# MB1-LED_BUTTON.net
KiCad netlist of a schematic drawn in Altium Designer
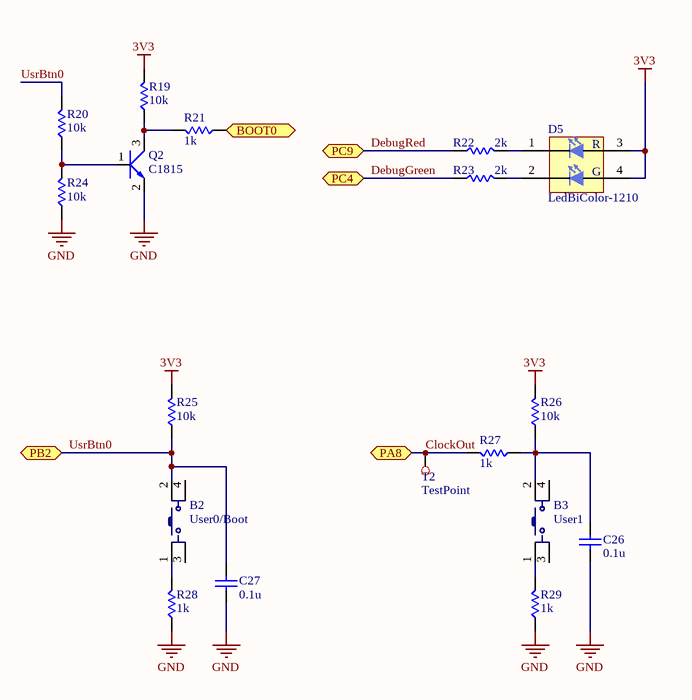
[diagram p0: MB1-LED_BUTTON.SchDoc]

(export (version "E")
  (design (tool "Eeschema 10.0.6"))
  (components
    (comp (ref "B2")
      (value "User0/Boot")
      (footprint "Horizon_SW_4pin_rectangular")
      (description "Tact switch")
      (libsource (lib "SMD_tact_sw") (part "Button"))
    )
    (comp (ref "B3")
      (value "User1")
      (footprint "Horizon_SW_4pin_rectangular")
      (description "Tact switch")
      (libsource (lib "SMD_tact_sw") (part "Button"))
    )
    (comp (ref "C26")
      (value "0.1u")
      (footprint "SM_0805_C_CERAMIC")
      (description "Non-polarity ceramic capacitor")
      (fields (field (name "Comment") "CAP_Ceramic") (field (name "PUBLISHER") "Altium Limited"))
      (libsource (lib "Copy of HLib_device_library") (part "C_Ceramic"))
    )
    (comp (ref "C27")
      (value "0.1u")
      (footprint "SM_0805_C_CERAMIC")
      (description "Non-polarity ceramic capacitor")
      (fields (field (name "Comment") "CAP_Ceramic") (field (name "PUBLISHER") "Altium Limited"))
      (libsource (lib "Copy of HLib_device_library") (part "C_Ceramic"))
    )
    (comp (ref "D5")
      (value "LedBiColor-1210")
      (footprint "Led-BiColor")
      (libsource (lib "MyLib") (part "LedBiColor-1210"))
    )
    (comp (ref "Q2") (value "C1815") (footprint "SOT23") (libsource (lib "MyLib") (part "C1815")))
    (comp (ref "R19")
      (value "10k")
      (footprint "SM_0805_R")
      (description "Resistor")
      (fields (field (name "PUBLISHER") "Altium Limited"))
      (libsource (lib "Copy of HLib_device_library") (part "R"))
    )
    (comp (ref "R20")
      (value "10k")
      (footprint "SM_0805_R")
      (description "Resistor")
      (fields (field (name "PUBLISHER") "Altium Limited"))
      (libsource (lib "Copy of HLib_device_library") (part "R"))
    )
    (comp (ref "R21")
      (value "1k")
      (footprint "SM_0805_R")
      (description "Resistor")
      (fields (field (name "PUBLISHER") "Altium Limited"))
      (libsource (lib "Copy of HLib_device_library") (part "R"))
    )
    (comp (ref "R22")
      (value "2k")
      (footprint "SM_0805_R")
      (description "Resistor")
      (fields (field (name "PUBLISHER") "Altium Limited"))
      (libsource (lib "Copy of HLib_device_library") (part "R"))
    )
    (comp (ref "R23")
      (value "2k")
      (footprint "SM_0805_R")
      (description "Resistor")
      (fields (field (name "PUBLISHER") "Altium Limited"))
      (libsource (lib "Copy of HLib_device_library") (part "R"))
    )
    (comp (ref "R24")
      (value "10k")
      (footprint "SM_0805_R")
      (description "Resistor")
      (fields (field (name "PUBLISHER") "Altium Limited"))
      (libsource (lib "Copy of HLib_device_library") (part "R"))
    )
    (comp (ref "R25")
      (value "10k")
      (footprint "SM_0805_R")
      (description "Resistor")
      (fields (field (name "PUBLISHER") "Altium Limited"))
      (libsource (lib "Copy of HLib_device_library") (part "R"))
    )
    (comp (ref "R26")
      (value "10k")
      (footprint "SM_0805_R")
      (description "Resistor")
      (fields (field (name "PUBLISHER") "Altium Limited"))
      (libsource (lib "Copy of HLib_device_library") (part "R"))
    )
    (comp (ref "R27")
      (value "1k")
      (footprint "SM_0805_R")
      (description "Resistor")
      (fields (field (name "PUBLISHER") "Altium Limited"))
      (libsource (lib "Copy of HLib_device_library") (part "R"))
    )
    (comp (ref "R28")
      (value "1k")
      (footprint "SM_0805_R")
      (description "Resistor")
      (fields (field (name "PUBLISHER") "Altium Limited"))
      (libsource (lib "Copy of HLib_device_library") (part "R"))
    )
    (comp (ref "R29")
      (value "1k")
      (footprint "SM_0805_R")
      (description "Resistor")
      (fields (field (name "PUBLISHER") "Altium Limited"))
      (libsource (lib "Copy of HLib_device_library") (part "R"))
    )
    (comp (ref "T2") (value "TestPoint") (footprint "TestPoint") (libsource (lib "MyLib") (part "TestPoint")))
  )
  (nets
    (net (code "1") (name "/BOOT0") (class "Default")
      (node (ref "R21") (pin "1") (pinfunction "1_1") (pintype "passive"))
    )
    (net (code "2") (name "/ClockOut") (class "Default")
      (node (ref "R27") (pin "2") (pinfunction "2_2") (pintype "passive"))
      (node (ref "T2") (pin "1") (pinfunction "0_1") (pintype "passive"))
    )
    (net (code "3") (name "/DebugGreen") (class "Default")
      (node (ref "R23") (pin "1") (pinfunction "1_1") (pintype "passive"))
    )
    (net (code "4") (name "/DebugRed") (class "Default")
      (node (ref "R22") (pin "1") (pinfunction "1_1") (pintype "passive"))
    )
    (net (code "5") (name "/UsrBtn0") (class "Default")
      (node (ref "B2") (pin "2") (pintype "passive"))
      (node (ref "C27") (pin "2") (pinfunction "2_2") (pintype "passive"))
      (node (ref "R20") (pin "2") (pinfunction "2_2") (pintype "passive"))
      (node (ref "R25") (pin "1") (pinfunction "1_1") (pintype "passive"))
    )
    (net (code "6") (name "3V3") (class "Default")
      (node (ref "D5") (pin "3") (pinfunction "R+_3") (pintype "passive"))
      (node (ref "D5") (pin "4") (pinfunction "G+_4") (pintype "passive"))
      (node (ref "R19") (pin "2") (pinfunction "2_2") (pintype "passive"))
      (node (ref "R25") (pin "2") (pinfunction "2_2") (pintype "passive"))
      (node (ref "R26") (pin "2") (pinfunction "2_2") (pintype "passive"))
    )
    (net (code "7") (name "GND") (class "Default")
      (node (ref "C26") (pin "1") (pinfunction "1_1") (pintype "passive"))
      (node (ref "C27") (pin "1") (pinfunction "1_1") (pintype "passive"))
      (node (ref "Q2") (pin "2") (pinfunction "E_2") (pintype "passive"))
      (node (ref "R24") (pin "1") (pinfunction "1_1") (pintype "passive"))
      (node (ref "R28") (pin "1") (pinfunction "1_1") (pintype "passive"))
      (node (ref "R29") (pin "1") (pinfunction "1_1") (pintype "passive"))
    )
    (net (code "8") (name "Net-(B2-Pad1)") (class "Default")
      (node (ref "B2") (pin "1") (pintype "passive"))
      (node (ref "R28") (pin "2") (pinfunction "2_2") (pintype "passive"))
    )
    (net (code "9") (name "Net-(B3-Pad1)") (class "Default")
      (node (ref "B3") (pin "1") (pintype "passive"))
      (node (ref "R29") (pin "2") (pinfunction "2_2") (pintype "passive"))
    )
    (net (code "10") (name "Net-(B3-Pad2)") (class "Default")
      (node (ref "B3") (pin "2") (pintype "passive"))
      (node (ref "C26") (pin "2") (pinfunction "2_2") (pintype "passive"))
      (node (ref "R26") (pin "1") (pinfunction "1_1") (pintype "passive"))
      (node (ref "R27") (pin "1") (pinfunction "1_1") (pintype "passive"))
    )
    (net (code "11") (name "Net-(D5-G-)") (class "Default")
      (node (ref "D5") (pin "2") (pinfunction "G-_2") (pintype "passive"))
      (node (ref "R23") (pin "2") (pinfunction "2_2") (pintype "passive"))
    )
    (net (code "12") (name "Net-(D5-R-)") (class "Default")
      (node (ref "D5") (pin "1") (pinfunction "R-_1") (pintype "passive"))
      (node (ref "R22") (pin "2") (pinfunction "2_2") (pintype "passive"))
    )
    (net (code "13") (name "Net-(Q2-B)") (class "Default")
      (node (ref "Q2") (pin "1") (pinfunction "B_1") (pintype "passive"))
      (node (ref "R20") (pin "1") (pinfunction "1_1") (pintype "passive"))
      (node (ref "R24") (pin "2") (pinfunction "2_2") (pintype "passive"))
    )
    (net (code "14") (name "Net-(Q2-C)") (class "Default")
      (node (ref "Q2") (pin "3") (pinfunction "C_3") (pintype "passive"))
      (node (ref "R19") (pin "1") (pinfunction "1_1") (pintype "passive"))
      (node (ref "R21") (pin "2") (pinfunction "2_2") (pintype "passive"))
    )
    (net (code "15") (name "unconnected-(B2-Pad3)") (class "Default")
      (node (ref "B2") (pin "3") (pintype "passive"))
    )
    (net (code "16") (name "unconnected-(B2-Pad4)") (class "Default")
      (node (ref "B2") (pin "4") (pintype "passive"))
    )
    (net (code "17") (name "unconnected-(B3-Pad3)") (class "Default")
      (node (ref "B3") (pin "3") (pintype "passive"))
    )
    (net (code "18") (name "unconnected-(B3-Pad4)") (class "Default")
      (node (ref "B3") (pin "4") (pintype "passive"))
    )
  )
)
